# HGS_Reflector.net
KiCad netlist of a schematic drawn in EAGLE
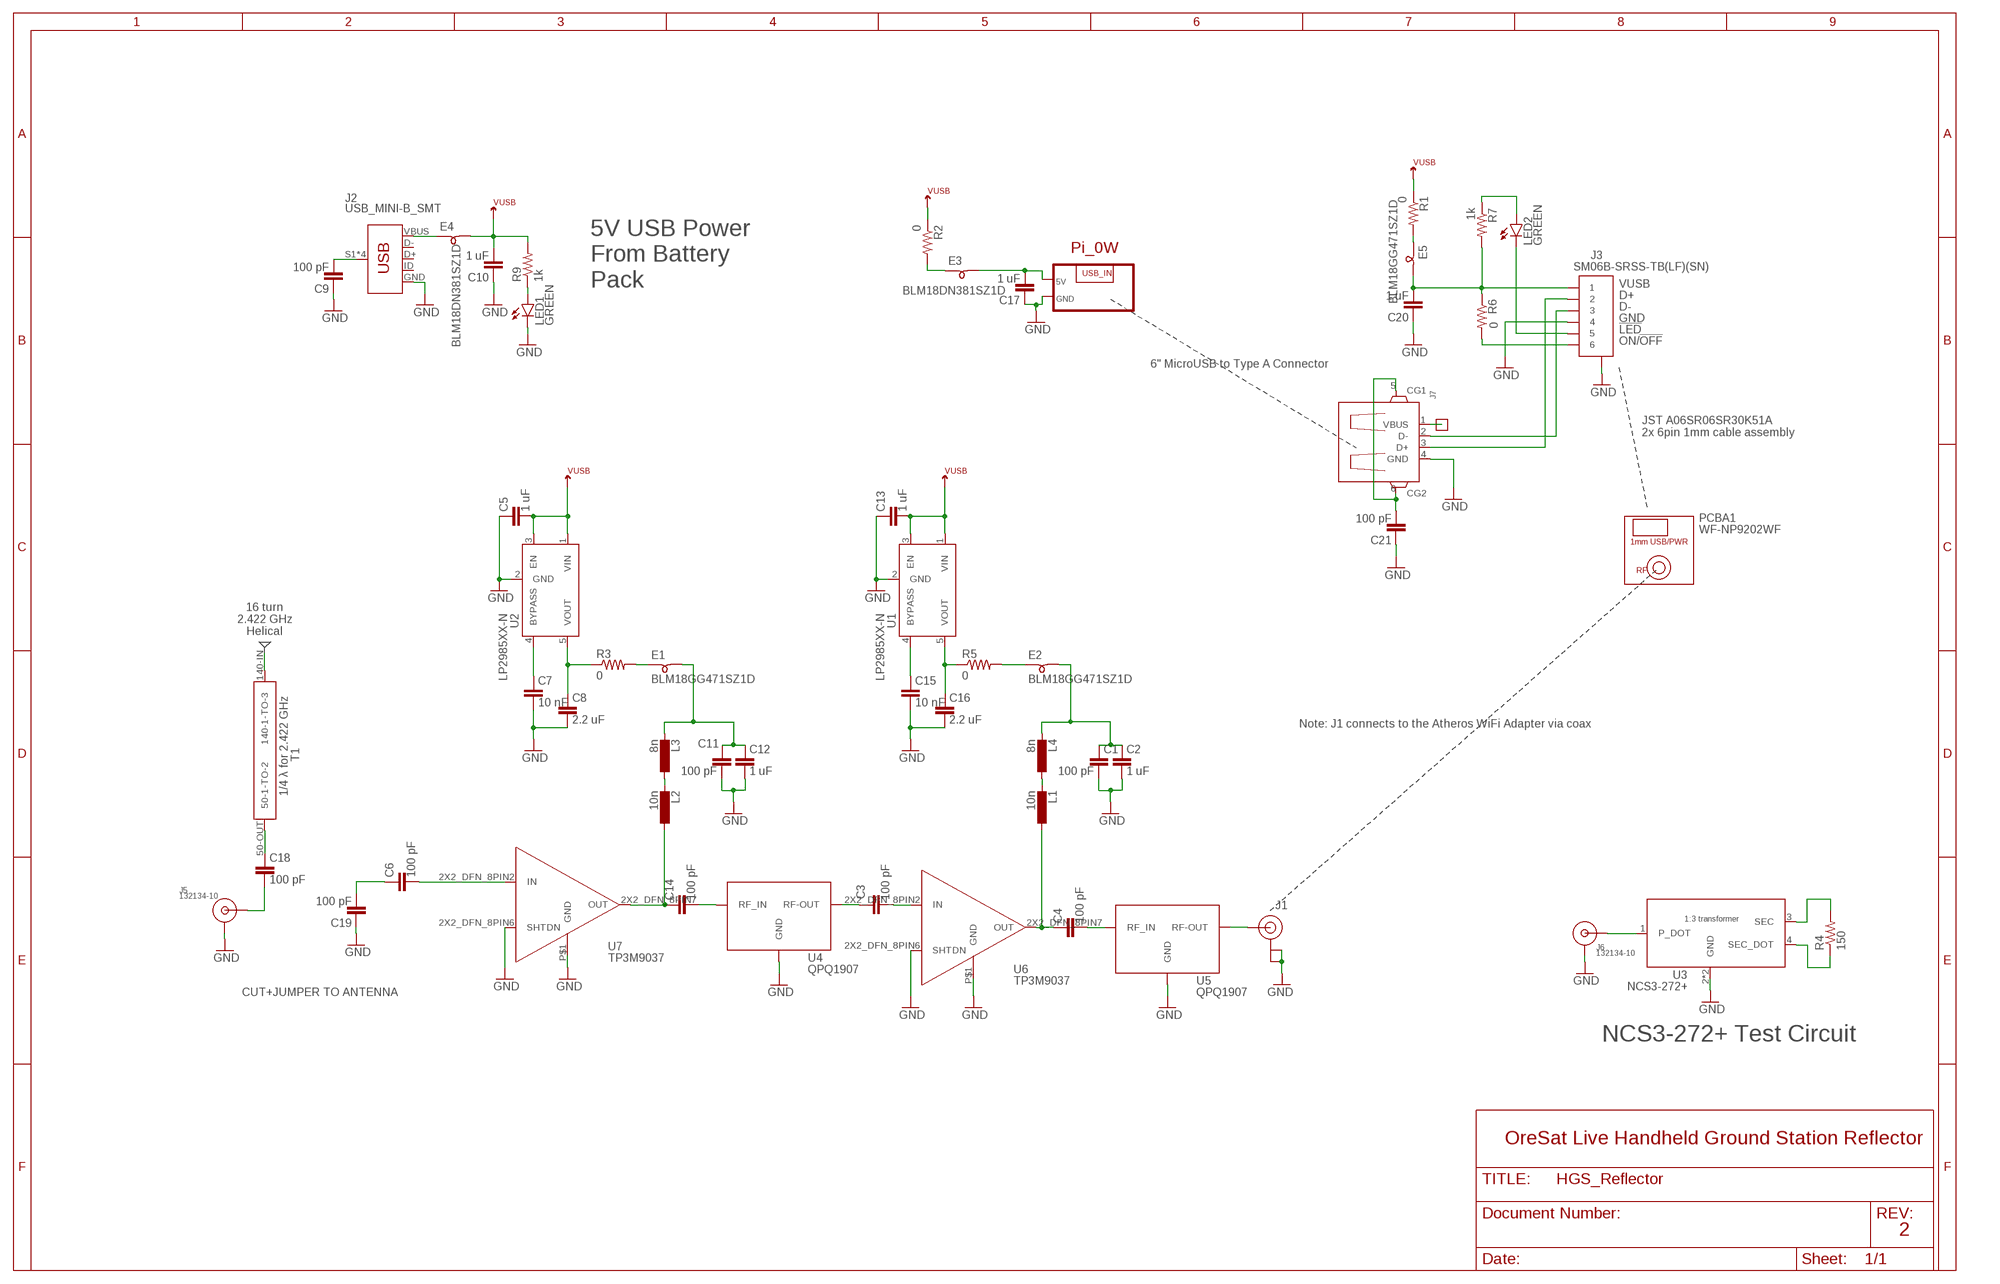
[diagram p0: schematic, sheet 1]

(export (version "E")
  (design (tool "Eeschema 10.0.6"))
  (components
    (comp (ref "C1")
      (value "100 pF")
      (footprint "eagle-import:.0603-C-NOSILK")
      (libsource (lib "eagle-import") (part "C-EU0603-C-NOSILK"))
    )
    (comp (ref "C2")
      (value "1 uF")
      (footprint "eagle-import:.0603-C-NOSILK")
      (libsource (lib "eagle-import") (part "C-EU0603-C-NOSILK"))
    )
    (comp (ref "C3")
      (value "100 pF")
      (footprint "eagle-import:.0402-C-NOSILK")
      (libsource (lib "eagle-import") (part "C-EU0402-C-NOSILK"))
    )
    (comp (ref "C4")
      (value "100 pF")
      (footprint "eagle-import:.0402-C-NOSILK")
      (libsource (lib "eagle-import") (part "C-EU0402-C-NOSILK"))
    )
    (comp (ref "C5")
      (value "1 uF")
      (footprint "eagle-import:.0603-B-NOSILK")
      (libsource (lib "eagle-import") (part "C-EU0603-B-NOSILK"))
    )
    (comp (ref "C6")
      (value "100 pF")
      (footprint "eagle-import:.0402-C-NOSILK")
      (libsource (lib "eagle-import") (part "C-EU0402-C-NOSILK"))
    )
    (comp (ref "C7")
      (value "10 nF")
      (footprint "eagle-import:.0603-B-NOSILK")
      (libsource (lib "eagle-import") (part "C-EU0603-B-NOSILK"))
    )
    (comp (ref "C8")
      (value "2.2 uF")
      (footprint "eagle-import:.0603-B-NOSILK")
      (libsource (lib "eagle-import") (part "C-EU0603-B-NOSILK"))
    )
    (comp (ref "C9")
      (value "100 pF")
      (footprint "eagle-import:.0603-C-NOSILK")
      (libsource (lib "eagle-import") (part "C-EU0603-C-NOSILK"))
    )
    (comp (ref "C10")
      (value "1 uF")
      (footprint "eagle-import:.0603-B-NOSILK")
      (libsource (lib "eagle-import") (part "C-EU0603-B-NOSILK"))
    )
    (comp (ref "C11")
      (value "100 pF")
      (footprint "eagle-import:.0603-C-NOSILK")
      (libsource (lib "eagle-import") (part "C-EU0603-C-NOSILK"))
    )
    (comp (ref "C12")
      (value "1 uF")
      (footprint "eagle-import:.0603-C-NOSILK")
      (libsource (lib "eagle-import") (part "C-EU0603-C-NOSILK"))
    )
    (comp (ref "C13")
      (value "1 uF")
      (footprint "eagle-import:.0603-B-NOSILK")
      (libsource (lib "eagle-import") (part "C-EU0603-B-NOSILK"))
    )
    (comp (ref "C14")
      (value "100 pF")
      (footprint "eagle-import:.0402-C-NOSILK")
      (libsource (lib "eagle-import") (part "C-EU0402-C-NOSILK"))
    )
    (comp (ref "C15")
      (value "10 nF")
      (footprint "eagle-import:.0603-B-NOSILK")
      (libsource (lib "eagle-import") (part "C-EU0603-B-NOSILK"))
    )
    (comp (ref "C16")
      (value "2.2 uF")
      (footprint "eagle-import:.0603-B-NOSILK")
      (libsource (lib "eagle-import") (part "C-EU0603-B-NOSILK"))
    )
    (comp (ref "C17")
      (value "1 uF")
      (footprint "eagle-import:.0603-B-NOSILK")
      (libsource (lib "eagle-import") (part "C-EU0603-B-NOSILK"))
    )
    (comp (ref "C18")
      (value "100 pF")
      (footprint "eagle-import:.0402-C-NOSILK")
      (libsource (lib "eagle-import") (part "C-EU0402-C-NOSILK"))
    )
    (comp (ref "C19")
      (value "100 pF")
      (footprint "eagle-import:.0402-C-NOSILK")
      (libsource (lib "eagle-import") (part "C-EU0402-C-NOSILK"))
    )
    (comp (ref "C20")
      (value "1 uF")
      (footprint "eagle-import:.0603-B-NOSILK")
      (libsource (lib "eagle-import") (part "C-EU0603-B-NOSILK"))
    )
    (comp (ref "C21")
      (value "100 pF")
      (footprint "eagle-import:.0603-C-NOSILK")
      (libsource (lib "eagle-import") (part "C-EU0603-C-NOSILK"))
    )
    (comp (ref "E1")
      (value "BLM18GG471SZ1D")
      (footprint "eagle-import:.0603-B")
      (libsource (lib "eagle-import") (part "L-BEAD-0603-B"))
    )
    (comp (ref "E2")
      (value "BLM18GG471SZ1D")
      (footprint "eagle-import:.0603-B")
      (libsource (lib "eagle-import") (part "L-BEAD-0603-B"))
    )
    (comp (ref "E3")
      (value "BLM18DN381SZ1D")
      (footprint "eagle-import:.0603-B")
      (libsource (lib "eagle-import") (part "L-BEAD-0603-B"))
    )
    (comp (ref "E4")
      (value "BLM18DN381SZ1D")
      (footprint "eagle-import:.0603-B")
      (libsource (lib "eagle-import") (part "L-BEAD-0603-B"))
    )
    (comp (ref "E5")
      (value "BLM18GG471SZ1D")
      (footprint "eagle-import:.0603-B")
      (libsource (lib "eagle-import") (part "L-BEAD-0603-B"))
    )
    (comp (ref "J1")
      (value "U.FL")
      (footprint "eagle-import:U.FL")
      (libsource (lib "eagle-import") (part "U.FL"))
    )
    (comp (ref "J2")
      (value "USB_MINI-B_SMT")
      (footprint "eagle-import:USB-MINIB")
      (libsource (lib "eagle-import") (part "USB_MINI-B_SMT"))
    )
    (comp (ref "J3")
      (value "SM06B-SRSS-TB(LF)(SN)")
      (footprint "eagle-import:CONN_SM06B-SRSS-TB_JST")
      (fields (field (name "COPYRIGHT") "Copyright (C) 2018 Accelerated Designs. All rights reserved"))
      (libsource (lib "eagle-import") (part "SM06B-SRSS-TB(LF)(SN)"))
    )
    (comp (ref "J5")
      (value "132134-10")
      (footprint "eagle-import:132134-10")
      (libsource (lib "eagle-import") (part "132134-10"))
    )
    (comp (ref "J6")
      (value "132134-10")
      (footprint "eagle-import:132134-10")
      (libsource (lib "eagle-import") (part "132134-10"))
    )
    (comp (ref "J7")
      (value "USB_HOST_W/CHASSIS_GND")
      (footprint "eagle-import:GHI2_USB_HOST_HORIZONTAL_W_CHASSIS_GND")
      (libsource (lib "eagle-import") (part "USB_HOST_W/CHASSIS_GND"))
    )
    (comp (ref "L1")
      (value "10n")
      (footprint "eagle-import:L3216C")
      (fields (field (name "SPICEPREFIX") "L") (field (name "IMPEDANCE") "10 nH"))
      (libsource (lib "eagle-import") (part "L-EUL3216C"))
    )
    (comp (ref "L2")
      (value "10n")
      (footprint "eagle-import:L3216C")
      (fields (field (name "SPICEPREFIX") "10 nH"))
      (libsource (lib "eagle-import") (part "L-EUL3216C"))
    )
    (comp (ref "L3")
      (value "8n")
      (footprint "eagle-import:L3216C")
      (fields (field (name "SPICEPREFIX") "L") (field (name "IMPEDANCE") "8 nH"))
      (libsource (lib "eagle-import") (part "L-EUL3216C"))
    )
    (comp (ref "L4")
      (value "8n")
      (footprint "eagle-import:L3216C")
      (fields (field (name "SPICEPREFIX") "L") (field (name "IMPEDANCE") "8 nH"))
      (libsource (lib "eagle-import") (part "L-EUL3216C"))
    )
    (comp (ref "LED1")
      (value "GREEN")
      (footprint "eagle-import:LED-0603")
      (libsource (lib "eagle-import") (part "LED-GREEN0603"))
    )
    (comp (ref "LED2")
      (value "GREEN")
      (footprint "eagle-import:LED-0603")
      (libsource (lib "eagle-import") (part "LED-GREEN0603"))
    )
    (comp (ref "PCBA1")
      (value "WF-NP9202WF")
      (footprint "eagle-import:WF-NP9202")
      (libsource (lib "eagle-import") (part "WF-NP9202WF"))
    )
    (comp (ref "PCBA2")
      (value "RASP_PI_0WPI_0W")
      (footprint "eagle-import:RASP_PI_0W")
      (libsource (lib "eagle-import") (part "RASP_PI_0WPI_0W"))
    )
    (comp (ref "R1")
      (value "0")
      (footprint "eagle-import:.0603-B-NOSILK")
      (libsource (lib "eagle-import") (part "R-US_0603-B-NOSILK"))
    )
    (comp (ref "R2")
      (value "0")
      (footprint "eagle-import:.0603-B-NOSILK")
      (libsource (lib "eagle-import") (part "R-US_0603-B-NOSILK"))
    )
    (comp (ref "R3")
      (value "0")
      (footprint "eagle-import:.0603-B-NOSILK")
      (libsource (lib "eagle-import") (part "R-US_0603-B-NOSILK"))
    )
    (comp (ref "R4")
      (value "150")
      (footprint "eagle-import:.0402-C-NOSILK")
      (libsource (lib "eagle-import") (part "R-US_0402-C-NOSILK"))
    )
    (comp (ref "R5")
      (value "0")
      (footprint "eagle-import:.0603-B-NOSILK")
      (libsource (lib "eagle-import") (part "R-US_0603-B-NOSILK"))
    )
    (comp (ref "R6")
      (value "0")
      (footprint "eagle-import:.0603-B-NOSILK")
      (libsource (lib "eagle-import") (part "R-US_0603-B-NOSILK"))
    )
    (comp (ref "R7")
      (value "1k")
      (footprint "eagle-import:.0603-B-NOSILK")
      (libsource (lib "eagle-import") (part "R-US_0603-B-NOSILK"))
    )
    (comp (ref "R9")
      (value "1k")
      (footprint "eagle-import:.0603-B-NOSILK")
      (libsource (lib "eagle-import") (part "R-US_0603-B-NOSILK"))
    )
    (comp (ref "T1")
      (value "QWT2.4222")
      (footprint "eagle-import:QWT_2.422G-V2")
      (libsource (lib "eagle-import") (part "QWT2.4222"))
    )
    (comp (ref "TP2")
      (value "TEST-POINT-LARGE-SQUARE")
      (footprint "eagle-import:1X01")
      (libsource (lib "eagle-import") (part "TEST-POINT-LARGE-SQUARE"))
    )
    (comp (ref "U1")
      (value "LP2985XX-N")
      (footprint "eagle-import:SOT-23")
      (libsource (lib "eagle-import") (part "LP2985XX-N"))
    )
    (comp (ref "U2")
      (value "LP2985XX-N")
      (footprint "eagle-import:SOT-23")
      (libsource (lib "eagle-import") (part "LP2985XX-N"))
    )
    (comp (ref "U3")
      (value "NCS3-272+")
      (footprint "eagle-import:GE0805C-1")
      (libsource (lib "eagle-import") (part "NCS3-272+"))
    )
    (comp (ref "U4")
      (value "QPQ1907")
      (footprint "eagle-import:QPQ1907")
      (libsource (lib "eagle-import") (part "QPQ1907"))
    )
    (comp (ref "U5")
      (value "QPQ1907")
      (footprint "eagle-import:QPQ1907")
      (libsource (lib "eagle-import") (part "QPQ1907"))
    )
    (comp (ref "U6")
      (value "LNA-TP3M9037")
      (footprint "eagle-import:TP3M9037")
      (libsource (lib "eagle-import") (part "LNA-TP3M9037"))
    )
    (comp (ref "U7")
      (value "LNA-TP3M9037")
      (footprint "eagle-import:TP3M9037")
      (libsource (lib "eagle-import") (part "LNA-TP3M9037"))
    )
  )
  (nets
    (net (code "1") (name "GND") (class "Default")
      (node (ref "C1") (pin "2") (pinfunction "2_2") (pintype "passive"))
      (node (ref "C10") (pin "1") (pinfunction "1_1") (pintype "passive"))
      (node (ref "C11") (pin "2") (pinfunction "2_2") (pintype "passive"))
      (node (ref "C12") (pin "2") (pinfunction "2_2") (pintype "passive"))
      (node (ref "C13") (pin "1") (pinfunction "1_1") (pintype "passive"))
      (node (ref "C15") (pin "2") (pinfunction "2_2") (pintype "passive"))
      (node (ref "C16") (pin "2") (pinfunction "2_2") (pintype "passive"))
      (node (ref "C17") (pin "1") (pinfunction "1_1") (pintype "passive"))
      (node (ref "C19") (pin "1") (pinfunction "1_1") (pintype "passive"))
      (node (ref "C2") (pin "2") (pinfunction "2_2") (pintype "passive"))
      (node (ref "C20") (pin "1") (pinfunction "1_1") (pintype "passive"))
      (node (ref "C21") (pin "1") (pinfunction "1_1") (pintype "passive"))
      (node (ref "C5") (pin "1") (pinfunction "1_1") (pintype "passive"))
      (node (ref "C7") (pin "2") (pinfunction "2_2") (pintype "passive"))
      (node (ref "C8") (pin "2") (pinfunction "2_2") (pintype "passive"))
      (node (ref "C9") (pin "1") (pinfunction "1_1") (pintype "passive"))
      (node (ref "J1") (pin "1") (pinfunction "GND_1") (pintype "bidirectional"))
      (node (ref "J1") (pin "2") (pinfunction "GND_2") (pintype "bidirectional"))
      (node (ref "J2") (pin "GND") (pinfunction "GND_GND") (pintype "power_in"))
      (node (ref "J3") (pin "4") (pinfunction "4_4") (pintype "passive"))
      (node (ref "J3") (pin "7") (pinfunction "7_7") (pintype "passive"))
      (node (ref "J3") (pin "8") (pinfunction "7_8") (pintype "passive"))
      (node (ref "J5") (pin "SHIELD") (pinfunction "GND_SHIELD") (pintype "passive"))
      (node (ref "J6") (pin "SHIELD") (pinfunction "GND_SHIELD") (pintype "passive"))
      (node (ref "J7") (pin "4") (pinfunction "GND_4") (pintype "bidirectional"))
      (node (ref "LED1") (pin "C") (pinfunction "C_C") (pintype "passive"))
      (node (ref "PCBA2") (pin "GND") (pinfunction "GND_GND") (pintype "bidirectional"))
      (node (ref "U1") (pin "2") (pinfunction "GND_2") (pintype "power_in"))
      (node (ref "U2") (pin "2") (pinfunction "GND_2") (pintype "power_in"))
      (node (ref "U3") (pin "2") (pinfunction "GND_2") (pintype "power_in"))
      (node (ref "U3") (pin "5") (pinfunction "GND_5") (pintype "power_in"))
      (node (ref "U4") (pin "GND") (pinfunction "GND_GND") (pintype "power_in"))
      (node (ref "U4") (pin "GND2") (pinfunction "GND_GND2") (pintype "power_in"))
      (node (ref "U4") (pin "GND3") (pinfunction "GND_GND3") (pintype "power_in"))
      (node (ref "U5") (pin "GND") (pinfunction "GND_GND") (pintype "power_in"))
      (node (ref "U5") (pin "GND2") (pinfunction "GND_GND2") (pintype "power_in"))
      (node (ref "U5") (pin "GND3") (pinfunction "GND_GND3") (pintype "power_in"))
      (node (ref "U6") (pin "2X2_DFN_8PIN6") (pinfunction "SHTDN_2X2_DFN_8PIN6") (pintype "power_in"))
      (node (ref "U6") (pin "P$1") (pinfunction "GND_P$1") (pintype "power_in"))
      (node (ref "U7") (pin "2X2_DFN_8PIN6") (pinfunction "SHTDN_2X2_DFN_8PIN6") (pintype "power_in"))
      (node (ref "U7") (pin "P$1") (pinfunction "GND_P$1") (pintype "power_in"))
    )
    (net (code "2") (name "Net-(C1-Pad1)") (class "Default")
      (node (ref "C1") (pin "1") (pinfunction "1_1") (pintype "passive"))
      (node (ref "C2") (pin "1") (pinfunction "1_1") (pintype "passive"))
      (node (ref "E2") (pin "2") (pinfunction "2_2") (pintype "passive"))
      (node (ref "L4") (pin "2") (pinfunction "2_2") (pintype "passive"))
    )
    (net (code "3") (name "Net-(C9-Pad2)") (class "Default")
      (node (ref "C9") (pin "2") (pinfunction "2_2") (pintype "passive"))
      (node (ref "J2") (pin "S1") (pinfunction "SHIELD_S1") (pintype "bidirectional"))
      (node (ref "J2") (pin "S2") (pinfunction "SHIELD_S2") (pintype "bidirectional"))
      (node (ref "J2") (pin "S3") (pinfunction "SHIELD_S3") (pintype "bidirectional"))
      (node (ref "J2") (pin "S4") (pinfunction "SHIELD_S4") (pintype "bidirectional"))
    )
    (net (code "4") (name "Net-(C11-Pad1)") (class "Default")
      (node (ref "C11") (pin "1") (pinfunction "1_1") (pintype "passive"))
      (node (ref "C12") (pin "1") (pinfunction "1_1") (pintype "passive"))
      (node (ref "E1") (pin "2") (pinfunction "2_2") (pintype "passive"))
      (node (ref "L3") (pin "2") (pinfunction "2_2") (pintype "passive"))
    )
    (net (code "5") (name "Net-(C17-Pad2)") (class "Default")
      (node (ref "C17") (pin "2") (pinfunction "2_2") (pintype "passive"))
      (node (ref "E3") (pin "2") (pinfunction "2_2") (pintype "passive"))
      (node (ref "PCBA2") (pin "5V") (pinfunction "5V_5V") (pintype "bidirectional"))
    )
    (net (code "6") (name "Net-(C19-Pad2)") (class "Default")
      (node (ref "C19") (pin "2") (pinfunction "2_2") (pintype "passive"))
      (node (ref "C6") (pin "1") (pinfunction "1_1") (pintype "passive"))
    )
    (net (code "7") (name "Net-(C20-Pad2)") (class "Default")
      (node (ref "C20") (pin "2") (pinfunction "2_2") (pintype "passive"))
      (node (ref "E5") (pin "2") (pinfunction "2_2") (pintype "passive"))
      (node (ref "J3") (pin "1") (pinfunction "1_1") (pintype "passive"))
      (node (ref "R6") (pin "1") (pinfunction "1_1") (pintype "passive"))
      (node (ref "R7") (pin "2") (pinfunction "2_2") (pintype "passive"))
    )
    (net (code "8") (name "Net-(E1-Pad1)") (class "Default")
      (node (ref "E1") (pin "1") (pinfunction "1_1") (pintype "passive"))
      (node (ref "R3") (pin "2") (pinfunction "2_2") (pintype "passive"))
    )
    (net (code "9") (name "Net-(E2-Pad1)") (class "Default")
      (node (ref "E2") (pin "1") (pinfunction "1_1") (pintype "passive"))
      (node (ref "R5") (pin "2") (pinfunction "2_2") (pintype "passive"))
    )
    (net (code "10") (name "Net-(E3-Pad1)") (class "Default")
      (node (ref "E3") (pin "1") (pinfunction "1_1") (pintype "passive"))
      (node (ref "R2") (pin "2") (pinfunction "2_2") (pintype "passive"))
    )
    (net (code "11") (name "Net-(E4-Pad1)") (class "Default")
      (node (ref "E4") (pin "1") (pinfunction "1_1") (pintype "passive"))
      (node (ref "J2") (pin "VBUS") (pinfunction "VBUS_VBUS") (pintype "power_in"))
    )
    (net (code "12") (name "Net-(E5-Pad1)") (class "Default")
      (node (ref "E5") (pin "1") (pinfunction "1_1") (pintype "passive"))
      (node (ref "R1") (pin "2") (pinfunction "2_2") (pintype "passive"))
    )
    (net (code "13") (name "Net-(J1-SIGNAL)") (class "Default")
      (node (ref "J1") (pin "FEED") (pinfunction "SIGNAL_FEED") (pintype "bidirectional"))
      (node (ref "U5") (pin "OUTPUT") (pinfunction "RF-OUT_OUTPUT") (pintype "passive"))
    )
    (net (code "14") (name "Net-(J3-Pad5)") (class "Default")
      (node (ref "J3") (pin "5") (pinfunction "5_5") (pintype "passive"))
      (node (ref "LED2") (pin "C") (pinfunction "C_C") (pintype "passive"))
    )
    (net (code "15") (name "Net-(J3-Pad6)") (class "Default")
      (node (ref "J3") (pin "6") (pinfunction "6_6") (pintype "passive"))
      (node (ref "R6") (pin "2") (pinfunction "2_2") (pintype "passive"))
    )
    (net (code "16") (name "Net-(J5-SIG)") (class "Default")
      (node (ref "C18") (pin "2") (pinfunction "2_2") (pintype "passive"))
      (node (ref "J5") (pin "CENTER") (pinfunction "SIG_CENTER") (pintype "passive"))
    )
    (net (code "17") (name "Net-(J6-SIG)") (class "Default")
      (node (ref "J6") (pin "CENTER") (pinfunction "SIG_CENTER") (pintype "passive"))
      (node (ref "U3") (pin "1") (pinfunction "P_DOT_1") (pintype "passive"))
    )
    (net (code "18") (name "Net-(J7-CG1)") (class "Default")
      (node (ref "C21") (pin "2") (pinfunction "2_2") (pintype "passive"))
      (node (ref "J7") (pin "5") (pinfunction "CG1_5") (pintype "bidirectional"))
      (node (ref "J7") (pin "6") (pinfunction "CG2_6") (pintype "bidirectional"))
    )
    (net (code "19") (name "Net-(J7-D+)") (class "Default")
      (node (ref "J3") (pin "2") (pinfunction "2_2") (pintype "passive"))
      (node (ref "J7") (pin "3") (pinfunction "D+_3") (pintype "bidirectional"))
    )
    (net (code "20") (name "Net-(J7-D-)") (class "Default")
      (node (ref "J3") (pin "3") (pinfunction "3_3") (pintype "passive"))
      (node (ref "J7") (pin "2") (pinfunction "D-_2") (pintype "bidirectional"))
    )
    (net (code "21") (name "Net-(J7-VBUS)") (class "Default")
      (node (ref "J7") (pin "1") (pinfunction "VBUS_1") (pintype "bidirectional"))
      (node (ref "TP2") (pin "1") (pinfunction "1_1") (pintype "passive"))
    )
    (net (code "22") (name "Net-(L1-Pad2)") (class "Default")
      (node (ref "L1") (pin "2") (pinfunction "2_2") (pintype "passive"))
      (node (ref "L4") (pin "1") (pinfunction "1_1") (pintype "passive"))
    )
    (net (code "23") (name "Net-(L2-Pad2)") (class "Default")
      (node (ref "L2") (pin "2") (pinfunction "2_2") (pintype "passive"))
      (node (ref "L3") (pin "1") (pinfunction "1_1") (pintype "passive"))
    )
    (net (code "24") (name "Net-(LED1-PadA)") (class "Default")
      (node (ref "LED1") (pin "A") (pinfunction "A_A") (pintype "passive"))
      (node (ref "R9") (pin "1") (pinfunction "1_1") (pintype "passive"))
    )
    (net (code "25") (name "Net-(LED2-PadA)") (class "Default")
      (node (ref "LED2") (pin "A") (pinfunction "A_A") (pintype "passive"))
      (node (ref "R7") (pin "1") (pinfunction "1_1") (pintype "passive"))
    )
    (net (code "26") (name "Net-(T1-50-1-TO-2)") (class "Default")
      (node (ref "C18") (pin "1") (pinfunction "1_1") (pintype "passive"))
      (node (ref "T1") (pin "50-OUT") (pinfunction "50-1-TO-2_50-OUT") (pintype "passive"))
    )
    (net (code "27") (name "Net-(U1-BYPASS)") (class "Default")
      (node (ref "C15") (pin "1") (pinfunction "1_1") (pintype "passive"))
      (node (ref "U1") (pin "4") (pinfunction "BYPASS_4") (pintype "power_in"))
    )
    (net (code "28") (name "Net-(U1-VOUT)") (class "Default")
      (node (ref "C16") (pin "1") (pinfunction "1_1") (pintype "passive"))
      (node (ref "R5") (pin "1") (pinfunction "1_1") (pintype "passive"))
      (node (ref "U1") (pin "5") (pinfunction "VOUT_5") (pintype "power_in"))
    )
    (net (code "29") (name "Net-(U2-BYPASS)") (class "Default")
      (node (ref "C7") (pin "1") (pinfunction "1_1") (pintype "passive"))
      (node (ref "U2") (pin "4") (pinfunction "BYPASS_4") (pintype "power_in"))
    )
    (net (code "30") (name "Net-(U2-VOUT)") (class "Default")
      (node (ref "C8") (pin "1") (pinfunction "1_1") (pintype "passive"))
      (node (ref "R3") (pin "1") (pinfunction "1_1") (pintype "passive"))
      (node (ref "U2") (pin "5") (pinfunction "VOUT_5") (pintype "power_in"))
    )
    (net (code "31") (name "Net-(U3-SEC)") (class "Default")
      (node (ref "R4") (pin "2") (pinfunction "2_2") (pintype "passive"))
      (node (ref "U3") (pin "3") (pinfunction "SEC_3") (pintype "passive"))
    )
    (net (code "32") (name "Net-(U3-SEC_DOT)") (class "Default")
      (node (ref "R4") (pin "1") (pinfunction "1_1") (pintype "passive"))
      (node (ref "U3") (pin "4") (pinfunction "SEC_DOT_4") (pintype "passive"))
    )
    (net (code "33") (name "Net-(U4-RF-OUT)") (class "Default")
      (node (ref "C3") (pin "1") (pinfunction "1_1") (pintype "passive"))
      (node (ref "U4") (pin "OUTPUT") (pinfunction "RF-OUT_OUTPUT") (pintype "passive"))
    )
    (net (code "34") (name "Net-(U4-RF_IN)") (class "Default")
      (node (ref "C14") (pin "2") (pinfunction "2_2") (pintype "passive"))
      (node (ref "U4") (pin "INPUT") (pinfunction "RF_IN_INPUT") (pintype "passive"))
    )
    (net (code "35") (name "Net-(U5-RF_IN)") (class "Default")
      (node (ref "C4") (pin "2") (pinfunction "2_2") (pintype "passive"))
      (node (ref "U5") (pin "INPUT") (pinfunction "RF_IN_INPUT") (pintype "passive"))
    )
    (net (code "36") (name "Net-(U6-IN)") (class "Default")
      (node (ref "C3") (pin "2") (pinfunction "2_2") (pintype "passive"))
      (node (ref "U6") (pin "2X2_DFN_8PIN2") (pinfunction "IN_2X2_DFN_8PIN2") (pintype "bidirectional"))
    )
    (net (code "37") (name "Net-(U6-OUT)") (class "Default")
      (node (ref "C4") (pin "1") (pinfunction "1_1") (pintype "passive"))
      (node (ref "L1") (pin "1") (pinfunction "1_1") (pintype "passive"))
      (node (ref "U6") (pin "2X2_DFN_8PIN7") (pinfunction "OUT_2X2_DFN_8PIN7") (pintype "bidirectional"))
    )
    (net (code "38") (name "Net-(U7-IN)") (class "Default")
      (node (ref "C6") (pin "2") (pinfunction "2_2") (pintype "passive"))
      (node (ref "U7") (pin "2X2_DFN_8PIN2") (pinfunction "IN_2X2_DFN_8PIN2") (pintype "bidirectional"))
    )
    (net (code "39") (name "Net-(U7-OUT)") (class "Default")
      (node (ref "C14") (pin "1") (pinfunction "1_1") (pintype "passive"))
      (node (ref "L2") (pin "1") (pinfunction "1_1") (pintype "passive"))
      (node (ref "U7") (pin "2X2_DFN_8PIN7") (pinfunction "OUT_2X2_DFN_8PIN7") (pintype "bidirectional"))
    )
    (net (code "40") (name "VUSB") (class "Default")
      (node (ref "C10") (pin "2") (pinfunction "2_2") (pintype "passive"))
      (node (ref "C13") (pin "2") (pinfunction "2_2") (pintype "passive"))
      (node (ref "C5") (pin "2") (pinfunction "2_2") (pintype "passive"))
      (node (ref "E4") (pin "2") (pinfunction "2_2") (pintype "passive"))
      (node (ref "R1") (pin "1") (pinfunction "1_1") (pintype "passive"))
      (node (ref "R2") (pin "1") (pinfunction "1_1") (pintype "passive"))
      (node (ref "R9") (pin "2") (pinfunction "2_2") (pintype "passive"))
      (node (ref "U1") (pin "1") (pinfunction "VIN_1") (pintype "power_in"))
      (node (ref "U1") (pin "3") (pinfunction "EN_3") (pintype "input"))
      (node (ref "U2") (pin "1") (pinfunction "VIN_1") (pintype "power_in"))
      (node (ref "U2") (pin "3") (pinfunction "EN_3") (pintype "input"))
    )
    (net (code "41") (name "unconnected-(J2-PadD+)") (class "Default")
      (node (ref "J2") (pin "D+") (pinfunction "D+_D+") (pintype "bidirectional"))
    )
    (net (code "42") (name "unconnected-(J2-PadD-)") (class "Default")
      (node (ref "J2") (pin "D-") (pinfunction "D-_D-") (pintype "bidirectional"))
    )
    (net (code "43") (name "unconnected-(J2-PadID)") (class "Default")
      (node (ref "J2") (pin "ID") (pinfunction "ID_ID") (pintype "bidirectional"))
    )
    (net (code "44") (name "unconnected-(T1-140-1-TO-3-Pad140-IN)") (class "Default")
      (node (ref "T1") (pin "140-IN") (pinfunction "140-1-TO-3_140-IN") (pintype "passive"))
    )
  )
)
